# 2.net
KiCad netlist of a schematic drawn in Altium Designer
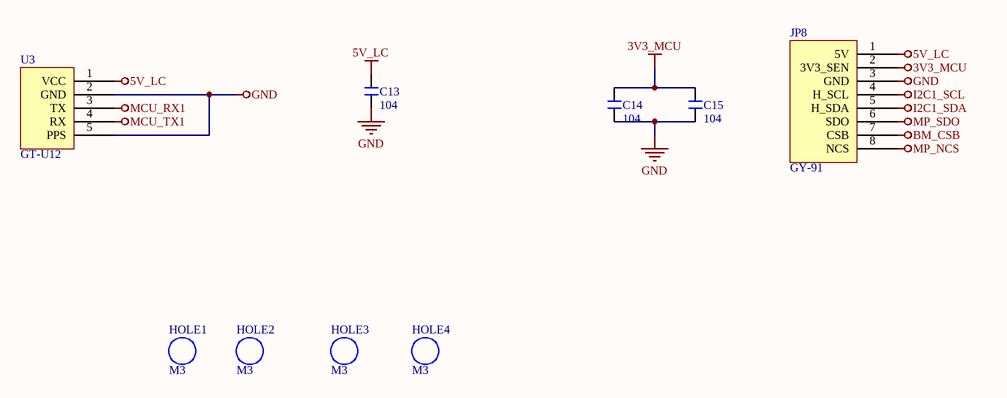
[diagram p0: 飞控主板2.SchDoc]

(export (version "E")
  (design (tool "Eeschema 10.0.6"))
  (components
    (comp (ref "C13")
      (value "104")
      (footprint "0603C")
      (description "无极性贴片电容")
      (fields (field (name "版权归属") "源创客"))
      (libsource (lib "ATKF405 V1.1") (part "C"))
    )
    (comp (ref "C14")
      (value "104")
      (footprint "0603C")
      (description "无极性贴片电容")
      (fields (field (name "版权归属") "源创客"))
      (libsource (lib "ATKF405 V1.1") (part "C"))
    )
    (comp (ref "C15")
      (value "104")
      (footprint "0603C")
      (description "无极性贴片电容")
      (fields (field (name "版权归属") "源创客"))
      (libsource (lib "ATKF405 V1.1") (part "C"))
    )
    (comp (ref "HOLE1")
      (value "M3")
      (footprint "M3 5.4MM")
      (description "铜柱孔")
      (fields (field (name "版权归属") "源创客"))
      (libsource (lib "STM32F407_CORE_BOARD") (part "M3"))
    )
    (comp (ref "HOLE2")
      (value "M3")
      (footprint "M3 5.4MM")
      (description "铜柱孔")
      (fields (field (name "版权归属") "源创客"))
      (libsource (lib "STM32F407_CORE_BOARD") (part "M3"))
    )
    (comp (ref "HOLE3")
      (value "M3")
      (footprint "M3 5.4MM")
      (description "铜柱孔")
      (fields (field (name "版权归属") "源创客"))
      (libsource (lib "STM32F407_CORE_BOARD") (part "M3"))
    )
    (comp (ref "HOLE4")
      (value "M3")
      (footprint "M3 5.4MM")
      (description "铜柱孔")
      (fields (field (name "版权归属") "源创客"))
      (libsource (lib "STM32F407_CORE_BOARD") (part "M3"))
    )
    (comp (ref "JP8")
      (value "GY-91")
      (footprint "GY-91")
      (description "优信电子GY-91接口，MPU9250+BMP280")
      (libsource (lib "飞控主板") (part "GY-91"))
    )
    (comp (ref "U3")
      (value "GT-U12")
      (footprint "GT-U12")
      (description "GPS模块")
      (libsource (lib "飞控主板") (part "GT-U12"))
    )
  )
  (nets
    (net (code "1") (name "3V3_MCU") (class "Default")
      (node (ref "C14") (pin "2") (pinfunction "2_2") (pintype "passive"))
      (node (ref "C15") (pin "2") (pinfunction "2_2") (pintype "passive"))
      (node (ref "JP8") (pin "2") (pinfunction "3V3_SEN_2") (pintype "passive"))
    )
    (net (code "2") (name "5V_LC") (class "Default")
      (node (ref "C13") (pin "2") (pinfunction "2_2") (pintype "passive"))
      (node (ref "JP8") (pin "1") (pinfunction "5V_1") (pintype "passive"))
      (node (ref "U3") (pin "1") (pinfunction "VCC_1") (pintype "passive"))
    )
    (net (code "3") (name "BM_CSB") (class "Default")
      (node (ref "JP8") (pin "7") (pinfunction "CSB_7") (pintype "passive"))
    )
    (net (code "4") (name "GND") (class "Default")
      (node (ref "C13") (pin "1") (pinfunction "1_1") (pintype "passive"))
      (node (ref "C14") (pin "1") (pinfunction "1_1") (pintype "passive"))
      (node (ref "C15") (pin "1") (pinfunction "1_1") (pintype "passive"))
      (node (ref "JP8") (pin "3") (pinfunction "GND_3") (pintype "passive"))
      (node (ref "U3") (pin "2") (pinfunction "GND_2") (pintype "passive"))
      (node (ref "U3") (pin "5") (pinfunction "PPS_5") (pintype "passive"))
    )
    (net (code "5") (name "I2C1_SCL") (class "Default")
      (node (ref "JP8") (pin "4") (pinfunction "H_SCL_4") (pintype "passive"))
    )
    (net (code "6") (name "I2C1_SDA") (class "Default")
      (node (ref "JP8") (pin "5") (pinfunction "H_SDA_5") (pintype "passive"))
    )
    (net (code "7") (name "MCU_RX1") (class "Default")
      (node (ref "U3") (pin "3") (pinfunction "TX_3") (pintype "passive"))
    )
    (net (code "8") (name "MCU_TX1") (class "Default")
      (node (ref "U3") (pin "4") (pinfunction "RX_4") (pintype "passive"))
    )
    (net (code "9") (name "MP_NCS") (class "Default")
      (node (ref "JP8") (pin "8") (pinfunction "NCS_8") (pintype "passive"))
    )
    (net (code "10") (name "MP_SDO") (class "Default")
      (node (ref "JP8") (pin "6") (pinfunction "SDO_6") (pintype "passive"))
    )
  )
)
